# eagleschem.net
KiCad netlist of a schematic drawn in EAGLE
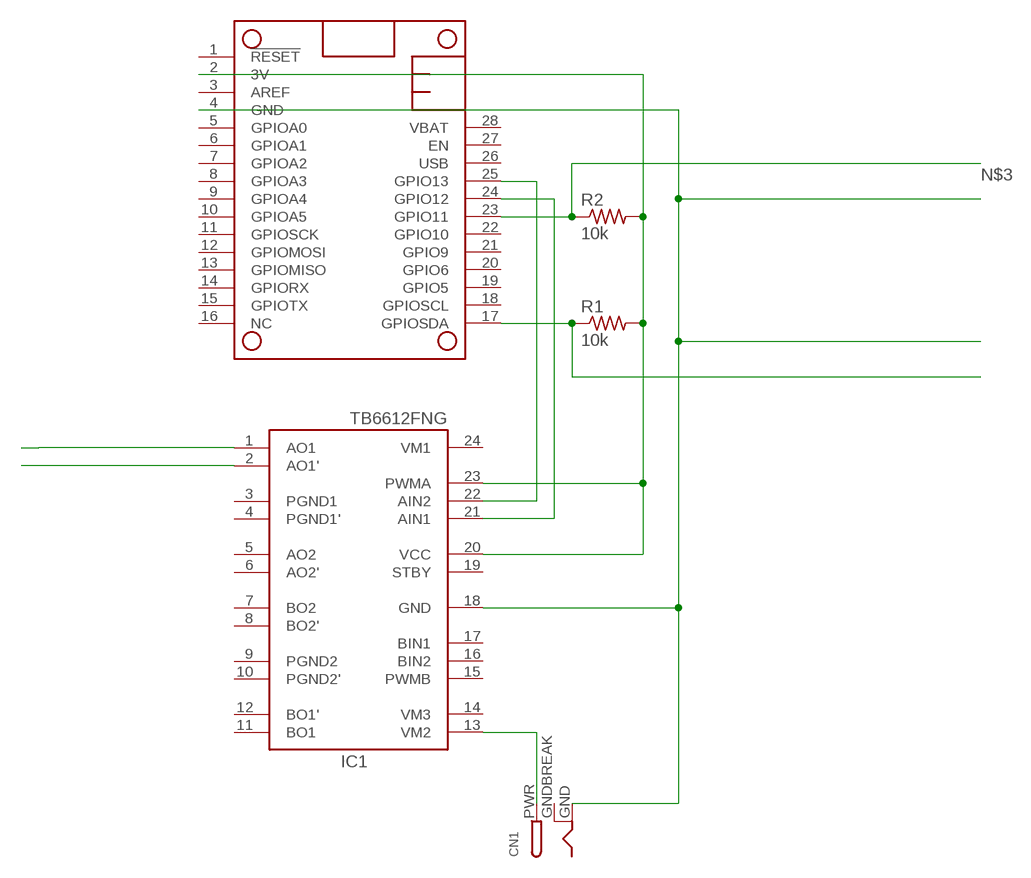
[diagram p0: schematic, sheet 1]

(export (version "E")
  (design (tool "Eeschema 10.0.6"))
  (components
    (comp (ref "CN1")
      (value "DCBARRELPTH")
      (footprint "eagle-import:DCJACK_2MM_PTH")
      (libsource (lib "eagle-import") (part "DCBARRELPTH"))
    )
    (comp (ref "IC1")
      (value "TB6612FNG")
      (footprint "eagle-import:SSOP24")
      (libsource (lib "eagle-import") (part "TB6612FNG"))
    )
    (comp (ref "MS1")
      (value "FEATHERWING")
      (footprint "eagle-import:FEATHERWING")
      (libsource (lib "eagle-import") (part "FEATHERWING"))
    )
    (comp (ref "R1")
      (value "10k")
      (footprint "eagle-import:0204V")
      (libsource (lib "eagle-import") (part "R-US_0204/2V"))
    )
    (comp (ref "R2")
      (value "10k")
      (footprint "eagle-import:0204V")
      (libsource (lib "eagle-import") (part "R-US_0204/2V"))
    )
  )
  (nets
    (net (code "1") (name "/GNDBREAK") (class "Default")
      (node (ref "CN1") (pin "GNDBREAK") (pinfunction "GNDBREAK_GNDBREAK") (pintype "power_in"))
    )
    (net (code "2") (name "/N$3") (class "Default")
      (node (ref "MS1") (pin "23") (pinfunction "GPIO11_23") (pintype "bidirectional"))
      (node (ref "R2") (pin "1") (pinfunction "1_1") (pintype "passive"))
    )
    (net (code "3") (name "/PGND1") (class "Default")
      (node (ref "IC1") (pin "3") (pinfunction "PGND1_3") (pintype "power_in"))
    )
    (net (code "4") (name "/PGND1'") (class "Default")
      (node (ref "IC1") (pin "4") (pinfunction "PGND1'_4") (pintype "power_in"))
    )
    (net (code "5") (name "/PGND2") (class "Default")
      (node (ref "IC1") (pin "9") (pinfunction "PGND2_9") (pintype "power_in"))
    )
    (net (code "6") (name "/PGND2'") (class "Default")
      (node (ref "IC1") (pin "10") (pinfunction "PGND2'_10") (pintype "power_in"))
    )
    (net (code "7") (name "/USB") (class "Default")
      (node (ref "MS1") (pin "26") (pinfunction "USB_26") (pintype "power_in"))
    )
    (net (code "8") (name "/VBAT") (class "Default")
      (node (ref "MS1") (pin "28") (pinfunction "VBAT_28") (pintype "power_in"))
    )
    (net (code "9") (name "/VM1") (class "Default")
      (node (ref "IC1") (pin "24") (pinfunction "VM1_24") (pintype "power_in"))
    )
    (net (code "10") (name "/VM3") (class "Default")
      (node (ref "IC1") (pin "14") (pinfunction "VM3_14") (pintype "power_in"))
    )
    (net (code "11") (name "Net-(IC1-AIN1)") (class "Default")
      (node (ref "IC1") (pin "21") (pinfunction "AIN1_21") (pintype "input"))
      (node (ref "MS1") (pin "24") (pinfunction "GPIO12_24") (pintype "bidirectional"))
    )
    (net (code "12") (name "Net-(IC1-AIN2)") (class "Default")
      (node (ref "IC1") (pin "22") (pinfunction "AIN2_22") (pintype "input"))
      (node (ref "MS1") (pin "25") (pinfunction "GPIO13_25") (pintype "bidirectional"))
    )
    (net (code "13") (name "Net-(IC1-GND)") (class "Default")
      (node (ref "CN1") (pin "GND") (pinfunction "GND_GND") (pintype "power_in"))
      (node (ref "IC1") (pin "18") (pinfunction "GND_18") (pintype "power_in"))
      (node (ref "MS1") (pin "4") (pinfunction "GND_4") (pintype "power_in"))
    )
    (net (code "14") (name "Net-(IC1-PWMA)") (class "Default")
      (node (ref "IC1") (pin "20") (pinfunction "VCC_20") (pintype "power_in"))
      (node (ref "IC1") (pin "23") (pinfunction "PWMA_23") (pintype "input"))
      (node (ref "MS1") (pin "2") (pinfunction "3V_2") (pintype "power_in"))
      (node (ref "R1") (pin "2") (pinfunction "2_2") (pintype "passive"))
      (node (ref "R2") (pin "2") (pinfunction "2_2") (pintype "passive"))
    )
    (net (code "15") (name "Net-(IC1-VM2)") (class "Default")
      (node (ref "CN1") (pin "PWR") (pinfunction "PWR_PWR") (pintype "power_in"))
      (node (ref "IC1") (pin "13") (pinfunction "VM2_13") (pintype "power_in"))
    )
    (net (code "16") (name "Net-(MS1-GPIOSDA)") (class "Default")
      (node (ref "MS1") (pin "17") (pinfunction "GPIOSDA_17") (pintype "bidirectional"))
      (node (ref "R1") (pin "1") (pinfunction "1_1") (pintype "passive"))
    )
    (net (code "17") (name "unconnected-(IC1-AO1'-Pad2)") (class "Default")
      (node (ref "IC1") (pin "2") (pinfunction "AO1'_2") (pintype "output"))
    )
    (net (code "18") (name "unconnected-(IC1-AO1-Pad1)") (class "Default")
      (node (ref "IC1") (pin "1") (pinfunction "AO1_1") (pintype "output"))
    )
    (net (code "19") (name "unconnected-(IC1-AO2'-Pad6)") (class "Default")
      (node (ref "IC1") (pin "6") (pinfunction "AO2'_6") (pintype "output"))
    )
    (net (code "20") (name "unconnected-(IC1-AO2-Pad5)") (class "Default")
      (node (ref "IC1") (pin "5") (pinfunction "AO2_5") (pintype "output"))
    )
    (net (code "21") (name "unconnected-(IC1-BIN1-Pad17)") (class "Default")
      (node (ref "IC1") (pin "17") (pinfunction "BIN1_17") (pintype "input"))
    )
    (net (code "22") (name "unconnected-(IC1-BIN2-Pad16)") (class "Default")
      (node (ref "IC1") (pin "16") (pinfunction "BIN2_16") (pintype "input"))
    )
    (net (code "23") (name "unconnected-(IC1-BO1'-Pad12)") (class "Default")
      (node (ref "IC1") (pin "12") (pinfunction "BO1'_12") (pintype "output"))
    )
    (net (code "24") (name "unconnected-(IC1-BO1-Pad11)") (class "Default")
      (node (ref "IC1") (pin "11") (pinfunction "BO1_11") (pintype "output"))
    )
    (net (code "25") (name "unconnected-(IC1-BO2'-Pad8)") (class "Default")
      (node (ref "IC1") (pin "8") (pinfunction "BO2'_8") (pintype "output"))
    )
    (net (code "26") (name "unconnected-(IC1-BO2-Pad7)") (class "Default")
      (node (ref "IC1") (pin "7") (pinfunction "BO2_7") (pintype "output"))
    )
    (net (code "27") (name "unconnected-(IC1-PWMB-Pad15)") (class "Default")
      (node (ref "IC1") (pin "15") (pinfunction "PWMB_15") (pintype "input"))
    )
    (net (code "28") (name "unconnected-(IC1-STBY-Pad19)") (class "Default")
      (node (ref "IC1") (pin "19") (pinfunction "STBY_19") (pintype "input"))
    )
    (net (code "29") (name "unconnected-(MS1-AREF-Pad3)") (class "Default")
      (node (ref "MS1") (pin "3") (pinfunction "AREF_3") (pintype "passive"))
    )
    (net (code "30") (name "unconnected-(MS1-EN-Pad27)") (class "Default")
      (node (ref "MS1") (pin "27") (pinfunction "EN_27") (pintype "passive"))
    )
    (net (code "31") (name "unconnected-(MS1-GPIO5-Pad19)") (class "Default")
      (node (ref "MS1") (pin "19") (pinfunction "GPIO5_19") (pintype "bidirectional"))
    )
    (net (code "32") (name "unconnected-(MS1-GPIO6-Pad20)") (class "Default")
      (node (ref "MS1") (pin "20") (pinfunction "GPIO6_20") (pintype "bidirectional"))
    )
    (net (code "33") (name "unconnected-(MS1-GPIO9-Pad21)") (class "Default")
      (node (ref "MS1") (pin "21") (pinfunction "GPIO9_21") (pintype "bidirectional"))
    )
    (net (code "34") (name "unconnected-(MS1-GPIO10-Pad22)") (class "Default")
      (node (ref "MS1") (pin "22") (pinfunction "GPIO10_22") (pintype "bidirectional"))
    )
    (net (code "35") (name "unconnected-(MS1-GPIOA0-Pad5)") (class "Default")
      (node (ref "MS1") (pin "5") (pinfunction "GPIOA0_5") (pintype "bidirectional"))
    )
    (net (code "36") (name "unconnected-(MS1-GPIOA1-Pad6)") (class "Default")
      (node (ref "MS1") (pin "6") (pinfunction "GPIOA1_6") (pintype "bidirectional"))
    )
    (net (code "37") (name "unconnected-(MS1-GPIOA2-Pad7)") (class "Default")
      (node (ref "MS1") (pin "7") (pinfunction "GPIOA2_7") (pintype "bidirectional"))
    )
    (net (code "38") (name "unconnected-(MS1-GPIOA3-Pad8)") (class "Default")
      (node (ref "MS1") (pin "8") (pinfunction "GPIOA3_8") (pintype "bidirectional"))
    )
    (net (code "39") (name "unconnected-(MS1-GPIOA4-Pad9)") (class "Default")
      (node (ref "MS1") (pin "9") (pinfunction "GPIOA4_9") (pintype "bidirectional"))
    )
    (net (code "40") (name "unconnected-(MS1-GPIOA5-Pad10)") (class "Default")
      (node (ref "MS1") (pin "10") (pinfunction "GPIOA5_10") (pintype "bidirectional"))
    )
    (net (code "41") (name "unconnected-(MS1-GPIOMISO-Pad13)") (class "Default")
      (node (ref "MS1") (pin "13") (pinfunction "GPIOMISO_13") (pintype "bidirectional"))
    )
    (net (code "42") (name "unconnected-(MS1-GPIOMOSI-Pad12)") (class "Default")
      (node (ref "MS1") (pin "12") (pinfunction "GPIOMOSI_12") (pintype "bidirectional"))
    )
    (net (code "43") (name "unconnected-(MS1-GPIORX-Pad14)") (class "Default")
      (node (ref "MS1") (pin "14") (pinfunction "GPIORX_14") (pintype "bidirectional"))
    )
    (net (code "44") (name "unconnected-(MS1-GPIOSCK-Pad11)") (class "Default")
      (node (ref "MS1") (pin "11") (pinfunction "GPIOSCK_11") (pintype "bidirectional"))
    )
    (net (code "45") (name "unconnected-(MS1-GPIOSCL-Pad18)") (class "Default")
      (node (ref "MS1") (pin "18") (pinfunction "GPIOSCL_18") (pintype "bidirectional"))
    )
    (net (code "46") (name "unconnected-(MS1-GPIOTX-Pad15)") (class "Default")
      (node (ref "MS1") (pin "15") (pinfunction "GPIOTX_15") (pintype "bidirectional"))
    )
    (net (code "47") (name "unconnected-(MS1-NC-Pad16)") (class "Default")
      (node (ref "MS1") (pin "16") (pinfunction "NC_16") (pintype "passive"))
    )
    (net (code "48") (name "unconnected-(MS1-~{RESET}-Pad1)") (class "Default")
      (node (ref "MS1") (pin "1") (pinfunction "~{RESET}_1") (pintype "input"))
    )
  )
)
